# SCH.net
KiCad netlist of a schematic drawn in Altium Designer
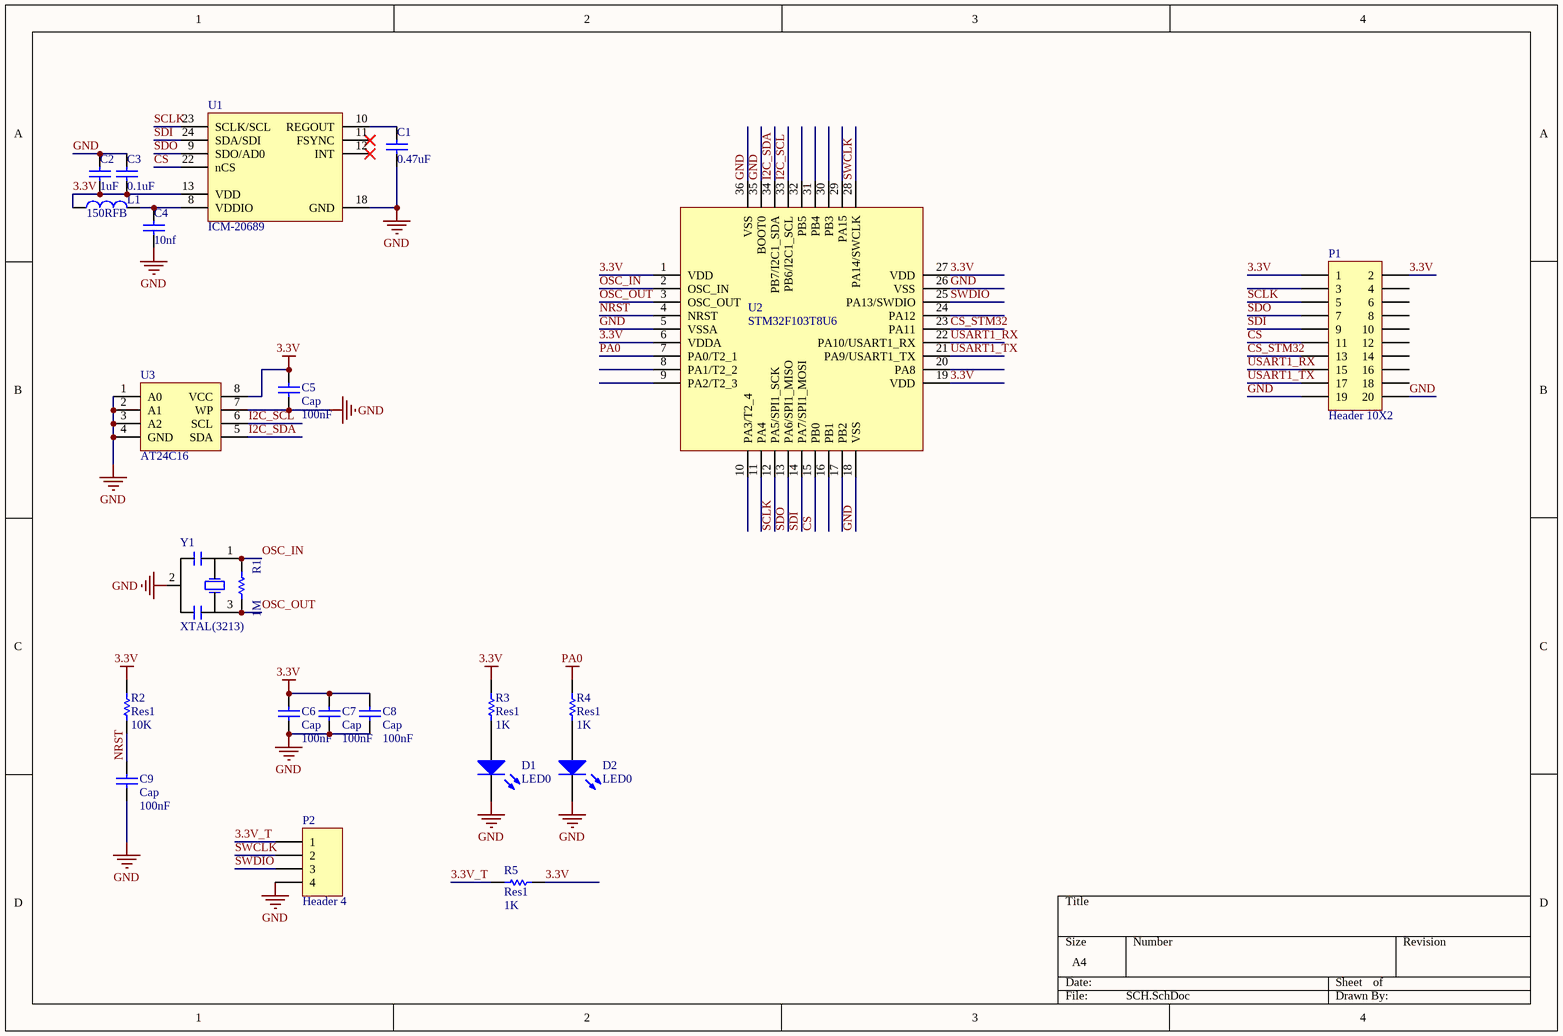
[diagram p0: SCH.SchDoc]

(export (version "E")
  (design (tool "Eeschema 10.0.6"))
  (components
    (comp (ref "C1")
      (value "0.47uF")
      (footprint "c0603")
      (description "Capacitor")
      (fields (field (name "Comment") "Cap") (field (name "PUBLISHER") "Altium Limited"))
      (libsource (lib "Miscellaneous Devices") (part "Cap"))
    )
    (comp (ref "C2")
      (value "1uF")
      (footprint "c0603")
      (description "Capacitor")
      (fields (field (name "Comment") "Cap") (field (name "PUBLISHER") "Altium Limited"))
      (libsource (lib "Miscellaneous Devices") (part "Cap"))
    )
    (comp (ref "C3")
      (value "0.1uF")
      (footprint "c0603")
      (description "Capacitor")
      (fields (field (name "Comment") "Cap") (field (name "PUBLISHER") "Altium Limited"))
      (libsource (lib "Miscellaneous Devices") (part "Cap"))
    )
    (comp (ref "C4")
      (value "10nf")
      (footprint "c0603")
      (description "Capacitor")
      (fields (field (name "Comment") "Cap") (field (name "PUBLISHER") "Altium Limited"))
      (libsource (lib "Miscellaneous Devices") (part "Cap"))
    )
    (comp (ref "C5")
      (value "Cap")
      (footprint "C0603")
      (description "Capacitor")
      (fields (field (name "ALTIUM_VALUE") "100nF") (field (name "PUBLISHER") "Altium Limited"))
      (libsource (lib "Miscellaneous Devices") (part "Cap"))
    )
    (comp (ref "C6")
      (value "Cap")
      (footprint "C0603")
      (description "Capacitor")
      (fields (field (name "ALTIUM_VALUE") "100nF") (field (name "PUBLISHER") "Altium Limited"))
      (libsource (lib "Miscellaneous Devices") (part "Cap"))
    )
    (comp (ref "C7")
      (value "Cap")
      (footprint "C0603")
      (description "Capacitor")
      (fields (field (name "ALTIUM_VALUE") "100nF") (field (name "PUBLISHER") "Altium Limited"))
      (libsource (lib "Miscellaneous Devices") (part "Cap"))
    )
    (comp (ref "C8")
      (value "Cap")
      (footprint "C0603")
      (description "Capacitor")
      (fields (field (name "ALTIUM_VALUE") "100nF") (field (name "PUBLISHER") "Altium Limited"))
      (libsource (lib "Miscellaneous Devices") (part "Cap"))
    )
    (comp (ref "C9")
      (value "Cap")
      (footprint "C0603")
      (description "Capacitor")
      (fields (field (name "ALTIUM_VALUE") "100nF") (field (name "PUBLISHER") "Altium Limited"))
      (libsource (lib "Miscellaneous Devices") (part "Cap"))
    )
    (comp (ref "D1")
      (value "LED0")
      (footprint "0603D")
      (description "Typical INFRARED GaAs LED")
      (fields (field (name "PUBLISHER") "Altium Limited"))
      (libsource (lib "Miscellaneous Devices") (part "LED0"))
    )
    (comp (ref "D2")
      (value "LED0")
      (footprint "0603D")
      (description "Typical INFRARED GaAs LED")
      (fields (field (name "PUBLISHER") "Altium Limited"))
      (libsource (lib "Miscellaneous Devices") (part "LED0"))
    )
    (comp (ref "L1")
      (value "150RFB")
      (footprint "r0603")
      (fields (field (name "Comment") "Inductors"))
      (libsource (lib "schlib_by_wjy") (part "Inductors"))
    )
    (comp (ref "P1")
      (value "Header 10X2")
      (footprint "0.5_2x10P")
      (description "Header, 10-Pin, Dual row")
      (fields (field (name "PUBLISHER") "Altium Limited"))
      (libsource (lib "Miscellaneous Connectors") (part "Header 10X2"))
    )
    (comp (ref "P2")
      (value "Header 4")
      (footprint "1.0*4PIN/SMD")
      (description "Header, 4-Pin")
      (fields (field (name "PUBLISHER") "Altium Limited"))
      (libsource (lib "Miscellaneous Connectors") (part "Header 4"))
    )
    (comp (ref "R1")
      (value "1M")
      (footprint "R0603")
      (description "Resistor")
      (fields (field (name "Comment") "Res1") (field (name "PUBLISHER") "Altium Limited"))
      (libsource (lib "Miscellaneous Devices") (part "Res1"))
    )
    (comp (ref "R2")
      (value "Res1")
      (footprint "R0603")
      (description "Resistor")
      (fields (field (name "ALTIUM_VALUE") "10K") (field (name "PUBLISHER") "Altium Limited"))
      (libsource (lib "Miscellaneous Devices") (part "Res1"))
    )
    (comp (ref "R3")
      (value "Res1")
      (footprint "R0603")
      (description "Resistor")
      (fields (field (name "ALTIUM_VALUE") "1K") (field (name "PUBLISHER") "Altium Limited"))
      (libsource (lib "Miscellaneous Devices") (part "Res1"))
    )
    (comp (ref "R4")
      (value "Res1")
      (footprint "R0603")
      (description "Resistor")
      (fields (field (name "ALTIUM_VALUE") "1K") (field (name "PUBLISHER") "Altium Limited"))
      (libsource (lib "Miscellaneous Devices") (part "Res1"))
    )
    (comp (ref "R5")
      (value "Res1")
      (footprint "R0603")
      (description "Resistor")
      (fields (field (name "ALTIUM_VALUE") "1K") (field (name "PUBLISHER") "Altium Limited"))
      (libsource (lib "Miscellaneous Devices") (part "Res1"))
    )
    (comp (ref "U1")
      (value "ICM-20689")
      (footprint "QFN24")
      (libsource (lib "schlib_by_wjy") (part "ICM-20689"))
    )
    (comp (ref "U2")
      (value "STM32F103T8U6")
      (footprint "VFQFPN36")
      (libsource (lib "四旋翼") (part "STM32F103T8U6"))
    )
    (comp (ref "U3") (value "AT24C16") (footprint "TSSOP8") (libsource (lib "四旋翼") (part "AT24C16")))
    (comp (ref "Y1")
      (value "XTAL(3213)")
      (footprint "Y3213")
      (description "Crystal Oscillator")
      (fields (field (name "PUBLISHER") "Altium Limited"))
      (libsource (lib "四旋翼") (part "XTAL(3213)"))
    )
  )
  (nets
    (net (code "1") (name "/3.3V_T") (class "Default")
      (node (ref "P2") (pin "1") (pinfunction "1_1") (pintype "passive"))
      (node (ref "R5") (pin "2") (pinfunction "2_2") (pintype "passive"))
    )
    (net (code "2") (name "/CS") (class "Default")
      (node (ref "P1") (pin "11") (pinfunction "11_11") (pintype "passive"))
      (node (ref "U1") (pin "22") (pinfunction "nCS_22") (pintype "passive"))
      (node (ref "U2") (pin "15") (pinfunction "PB0_15") (pintype "passive"))
    )
    (net (code "3") (name "/CS_STM32") (class "Default")
      (node (ref "P1") (pin "13") (pinfunction "13_13") (pintype "passive"))
      (node (ref "U2") (pin "23") (pinfunction "PA11_23") (pintype "passive"))
    )
    (net (code "4") (name "/I2C_SCL") (class "Default")
      (node (ref "U2") (pin "33") (pinfunction "PB6/I2C1_SCL_33") (pintype "passive"))
      (node (ref "U3") (pin "6") (pinfunction "SCL_6") (pintype "passive"))
    )
    (net (code "5") (name "/I2C_SDA") (class "Default")
      (node (ref "U2") (pin "34") (pinfunction "PB7/I2C1_SDA_34") (pintype "passive"))
      (node (ref "U3") (pin "5") (pinfunction "SDA_5") (pintype "passive"))
    )
    (net (code "6") (name "/NRST") (class "Default")
      (node (ref "C9") (pin "2") (pinfunction "2_2") (pintype "passive"))
      (node (ref "R2") (pin "1") (pinfunction "1_1") (pintype "passive"))
      (node (ref "U2") (pin "4") (pinfunction "NRST_4") (pintype "passive"))
    )
    (net (code "7") (name "/OSC_IN") (class "Default")
      (node (ref "R1") (pin "2") (pinfunction "2_2") (pintype "passive"))
      (node (ref "U2") (pin "2") (pinfunction "OSC_IN_2") (pintype "passive"))
      (node (ref "Y1") (pin "1") (pinfunction "OSC1_1") (pintype "passive"))
    )
    (net (code "8") (name "/OSC_OUT") (class "Default")
      (node (ref "R1") (pin "1") (pinfunction "1_1") (pintype "passive"))
      (node (ref "U2") (pin "3") (pinfunction "OSC_OUT_3") (pintype "passive"))
      (node (ref "Y1") (pin "3") (pinfunction "OSC2_3") (pintype "passive"))
    )
    (net (code "9") (name "/SCLK") (class "Default")
      (node (ref "P1") (pin "5") (pinfunction "5_5") (pintype "passive"))
      (node (ref "U1") (pin "23") (pinfunction "SCLK/SCL_23") (pintype "passive"))
      (node (ref "U2") (pin "12") (pinfunction "PA5/SPI1_SCK_12") (pintype "passive"))
    )
    (net (code "10") (name "/SDI") (class "Default")
      (node (ref "P1") (pin "9") (pinfunction "9_9") (pintype "passive"))
      (node (ref "U1") (pin "24") (pinfunction "SDA/SDI_24") (pintype "passive"))
      (node (ref "U2") (pin "14") (pinfunction "PA7/SPI1_MOSI_14") (pintype "passive"))
    )
    (net (code "11") (name "/SDO") (class "Default")
      (node (ref "P1") (pin "7") (pinfunction "7_7") (pintype "passive"))
      (node (ref "U1") (pin "9") (pinfunction "SDO/AD0_9") (pintype "passive"))
      (node (ref "U2") (pin "13") (pinfunction "PA6/SPI1_MISO_13") (pintype "passive"))
    )
    (net (code "12") (name "/SWCLK") (class "Default")
      (node (ref "P2") (pin "2") (pinfunction "2_2") (pintype "passive"))
      (node (ref "U2") (pin "28") (pinfunction "PA14/SWCLK_28") (pintype "passive"))
    )
    (net (code "13") (name "/SWDIO") (class "Default")
      (node (ref "P2") (pin "3") (pinfunction "3_3") (pintype "passive"))
      (node (ref "U2") (pin "25") (pinfunction "PA13/SWDIO_25") (pintype "passive"))
    )
    (net (code "14") (name "/USART1_RX") (class "Default")
      (node (ref "P1") (pin "15") (pinfunction "15_15") (pintype "passive"))
      (node (ref "U2") (pin "22") (pinfunction "PA10/USART1_RX_22") (pintype "passive"))
    )
    (net (code "15") (name "/USART1_TX") (class "Default")
      (node (ref "P1") (pin "17") (pinfunction "17_17") (pintype "passive"))
      (node (ref "U2") (pin "21") (pinfunction "PA9/USART1_TX_21") (pintype "passive"))
    )
    (net (code "16") (name "3.3V") (class "Default")
      (node (ref "C2") (pin "1") (pinfunction "1_1") (pintype "passive"))
      (node (ref "C3") (pin "1") (pinfunction "1_1") (pintype "passive"))
      (node (ref "C5") (pin "2") (pinfunction "2_2") (pintype "passive"))
      (node (ref "C6") (pin "2") (pinfunction "2_2") (pintype "passive"))
      (node (ref "C7") (pin "2") (pinfunction "2_2") (pintype "passive"))
      (node (ref "C8") (pin "2") (pinfunction "2_2") (pintype "passive"))
      (node (ref "L1") (pin "1") (pinfunction "1_1") (pintype "passive"))
      (node (ref "P1") (pin "1") (pinfunction "1_1") (pintype "passive"))
      (node (ref "P1") (pin "2") (pinfunction "2_2") (pintype "passive"))
      (node (ref "R2") (pin "2") (pinfunction "2_2") (pintype "passive"))
      (node (ref "R3") (pin "2") (pinfunction "2_2") (pintype "passive"))
      (node (ref "R5") (pin "1") (pinfunction "1_1") (pintype "passive"))
      (node (ref "U1") (pin "13") (pinfunction "VDD_13") (pintype "passive"))
      (node (ref "U2") (pin "1") (pinfunction "VDD_1") (pintype "passive"))
      (node (ref "U2") (pin "19") (pinfunction "VDD_19") (pintype "passive"))
      (node (ref "U2") (pin "27") (pinfunction "VDD_27") (pintype "passive"))
      (node (ref "U2") (pin "6") (pinfunction "VDDA_6") (pintype "passive"))
      (node (ref "U3") (pin "8") (pinfunction "VCC_8") (pintype "passive"))
    )
    (net (code "17") (name "GND") (class "Default")
      (node (ref "C1") (pin "1") (pinfunction "1_1") (pintype "passive"))
      (node (ref "C2") (pin "2") (pinfunction "2_2") (pintype "passive"))
      (node (ref "C3") (pin "2") (pinfunction "2_2") (pintype "passive"))
      (node (ref "C4") (pin "1") (pinfunction "1_1") (pintype "passive"))
      (node (ref "C5") (pin "1") (pinfunction "1_1") (pintype "passive"))
      (node (ref "C6") (pin "1") (pinfunction "1_1") (pintype "passive"))
      (node (ref "C7") (pin "1") (pinfunction "1_1") (pintype "passive"))
      (node (ref "C8") (pin "1") (pinfunction "1_1") (pintype "passive"))
      (node (ref "C9") (pin "1") (pinfunction "1_1") (pintype "passive"))
      (node (ref "D1") (pin "2") (pinfunction "K_2") (pintype "passive"))
      (node (ref "D2") (pin "2") (pinfunction "K_2") (pintype "passive"))
      (node (ref "P1") (pin "19") (pinfunction "19_19") (pintype "passive"))
      (node (ref "P1") (pin "20") (pinfunction "20_20") (pintype "passive"))
      (node (ref "P2") (pin "4") (pinfunction "4_4") (pintype "passive"))
      (node (ref "U1") (pin "18") (pinfunction "GND_18") (pintype "passive"))
      (node (ref "U2") (pin "18") (pinfunction "VSS_18") (pintype "passive"))
      (node (ref "U2") (pin "26") (pinfunction "VSS_26") (pintype "passive"))
      (node (ref "U2") (pin "35") (pinfunction "BOOT0_35") (pintype "passive"))
      (node (ref "U2") (pin "36") (pinfunction "VSS_36") (pintype "passive"))
      (node (ref "U2") (pin "5") (pinfunction "VSSA_5") (pintype "passive"))
      (node (ref "U3") (pin "1") (pinfunction "A0_1") (pintype "passive"))
      (node (ref "U3") (pin "2") (pinfunction "A1_2") (pintype "passive"))
      (node (ref "U3") (pin "3") (pinfunction "A2_3") (pintype "passive"))
      (node (ref "U3") (pin "4") (pinfunction "GND_4") (pintype "passive"))
      (node (ref "U3") (pin "7") (pinfunction "WP_7") (pintype "passive"))
      (node (ref "Y1") (pin "2") (pinfunction "GND_2") (pintype "passive"))
    )
    (net (code "18") (name "Net-(D1-A)") (class "Default")
      (node (ref "D1") (pin "1") (pinfunction "A_1") (pintype "passive"))
      (node (ref "R3") (pin "1") (pinfunction "1_1") (pintype "passive"))
    )
    (net (code "19") (name "Net-(D2-A)") (class "Default")
      (node (ref "D2") (pin "1") (pinfunction "A_1") (pintype "passive"))
      (node (ref "R4") (pin "1") (pinfunction "1_1") (pintype "passive"))
    )
    (net (code "20") (name "Net-(U1-REGOUT)") (class "Default")
      (node (ref "C1") (pin "2") (pinfunction "2_2") (pintype "passive"))
      (node (ref "U1") (pin "10") (pinfunction "REGOUT_10") (pintype "passive"))
    )
    (net (code "21") (name "Net-(U1-VDDIO)") (class "Default")
      (node (ref "C4") (pin "2") (pinfunction "2_2") (pintype "passive"))
      (node (ref "L1") (pin "2") (pinfunction "2_2") (pintype "passive"))
      (node (ref "U1") (pin "8") (pinfunction "VDDIO_8") (pintype "passive"))
    )
    (net (code "22") (name "PA0") (class "Default")
      (node (ref "R4") (pin "2") (pinfunction "2_2") (pintype "passive"))
      (node (ref "U2") (pin "7") (pinfunction "PA0/T2_1_7") (pintype "passive"))
    )
    (net (code "23") (name "unconnected-(P1-Pad3)") (class "Default")
      (node (ref "P1") (pin "3") (pinfunction "3_3") (pintype "passive"))
    )
    (net (code "24") (name "unconnected-(P1-Pad4)") (class "Default")
      (node (ref "P1") (pin "4") (pinfunction "4_4") (pintype "passive"))
    )
    (net (code "25") (name "unconnected-(P1-Pad6)") (class "Default")
      (node (ref "P1") (pin "6") (pinfunction "6_6") (pintype "passive"))
    )
    (net (code "26") (name "unconnected-(P1-Pad8)") (class "Default")
      (node (ref "P1") (pin "8") (pinfunction "8_8") (pintype "passive"))
    )
    (net (code "27") (name "unconnected-(P1-Pad10)") (class "Default")
      (node (ref "P1") (pin "10") (pinfunction "10_10") (pintype "passive"))
    )
    (net (code "28") (name "unconnected-(P1-Pad12)") (class "Default")
      (node (ref "P1") (pin "12") (pinfunction "12_12") (pintype "passive"))
    )
    (net (code "29") (name "unconnected-(P1-Pad14)") (class "Default")
      (node (ref "P1") (pin "14") (pinfunction "14_14") (pintype "passive"))
    )
    (net (code "30") (name "unconnected-(P1-Pad16)") (class "Default")
      (node (ref "P1") (pin "16") (pinfunction "16_16") (pintype "passive"))
    )
    (net (code "31") (name "unconnected-(P1-Pad18)") (class "Default")
      (node (ref "P1") (pin "18") (pinfunction "18_18") (pintype "passive"))
    )
    (net (code "32") (name "unconnected-(U1-FSYNC-Pad11)") (class "Default")
      (node (ref "U1") (pin "11") (pinfunction "FSYNC_11") (pintype "passive+no_connect"))
    )
    (net (code "33") (name "unconnected-(U1-INT-Pad12)") (class "Default")
      (node (ref "U1") (pin "12") (pinfunction "INT_12") (pintype "passive+no_connect"))
    )
    (net (code "34") (name "unconnected-(U2-PA1{slash}T2_2-Pad8)") (class "Default")
      (node (ref "U2") (pin "8") (pinfunction "PA1/T2_2_8") (pintype "passive"))
    )
    (net (code "35") (name "unconnected-(U2-PA2{slash}T2_3-Pad9)") (class "Default")
      (node (ref "U2") (pin "9") (pinfunction "PA2/T2_3_9") (pintype "passive"))
    )
    (net (code "36") (name "unconnected-(U2-PA3{slash}T2_4-Pad10)") (class "Default")
      (node (ref "U2") (pin "10") (pinfunction "PA3/T2_4_10") (pintype "passive"))
    )
    (net (code "37") (name "unconnected-(U2-PA4-Pad11)") (class "Default")
      (node (ref "U2") (pin "11") (pinfunction "PA4_11") (pintype "passive"))
    )
    (net (code "38") (name "unconnected-(U2-PA8-Pad20)") (class "Default")
      (node (ref "U2") (pin "20") (pinfunction "PA8_20") (pintype "passive"))
    )
    (net (code "39") (name "unconnected-(U2-PA12-Pad24)") (class "Default")
      (node (ref "U2") (pin "24") (pinfunction "PA12_24") (pintype "passive"))
    )
    (net (code "40") (name "unconnected-(U2-PA15-Pad29)") (class "Default")
      (node (ref "U2") (pin "29") (pinfunction "PA15_29") (pintype "passive"))
    )
    (net (code "41") (name "unconnected-(U2-PB1-Pad16)") (class "Default")
      (node (ref "U2") (pin "16") (pinfunction "PB1_16") (pintype "passive"))
    )
    (net (code "42") (name "unconnected-(U2-PB2-Pad17)") (class "Default")
      (node (ref "U2") (pin "17") (pinfunction "PB2_17") (pintype "passive"))
    )
    (net (code "43") (name "unconnected-(U2-PB3-Pad30)") (class "Default")
      (node (ref "U2") (pin "30") (pinfunction "PB3_30") (pintype "passive"))
    )
    (net (code "44") (name "unconnected-(U2-PB4-Pad31)") (class "Default")
      (node (ref "U2") (pin "31") (pinfunction "PB4_31") (pintype "passive"))
    )
    (net (code "45") (name "unconnected-(U2-PB5-Pad32)") (class "Default")
      (node (ref "U2") (pin "32") (pinfunction "PB5_32") (pintype "passive"))
    )
  )
)
